# SKAARDUINO_v3_1_bottom.net
KiCad netlist of a schematic drawn in EAGLE
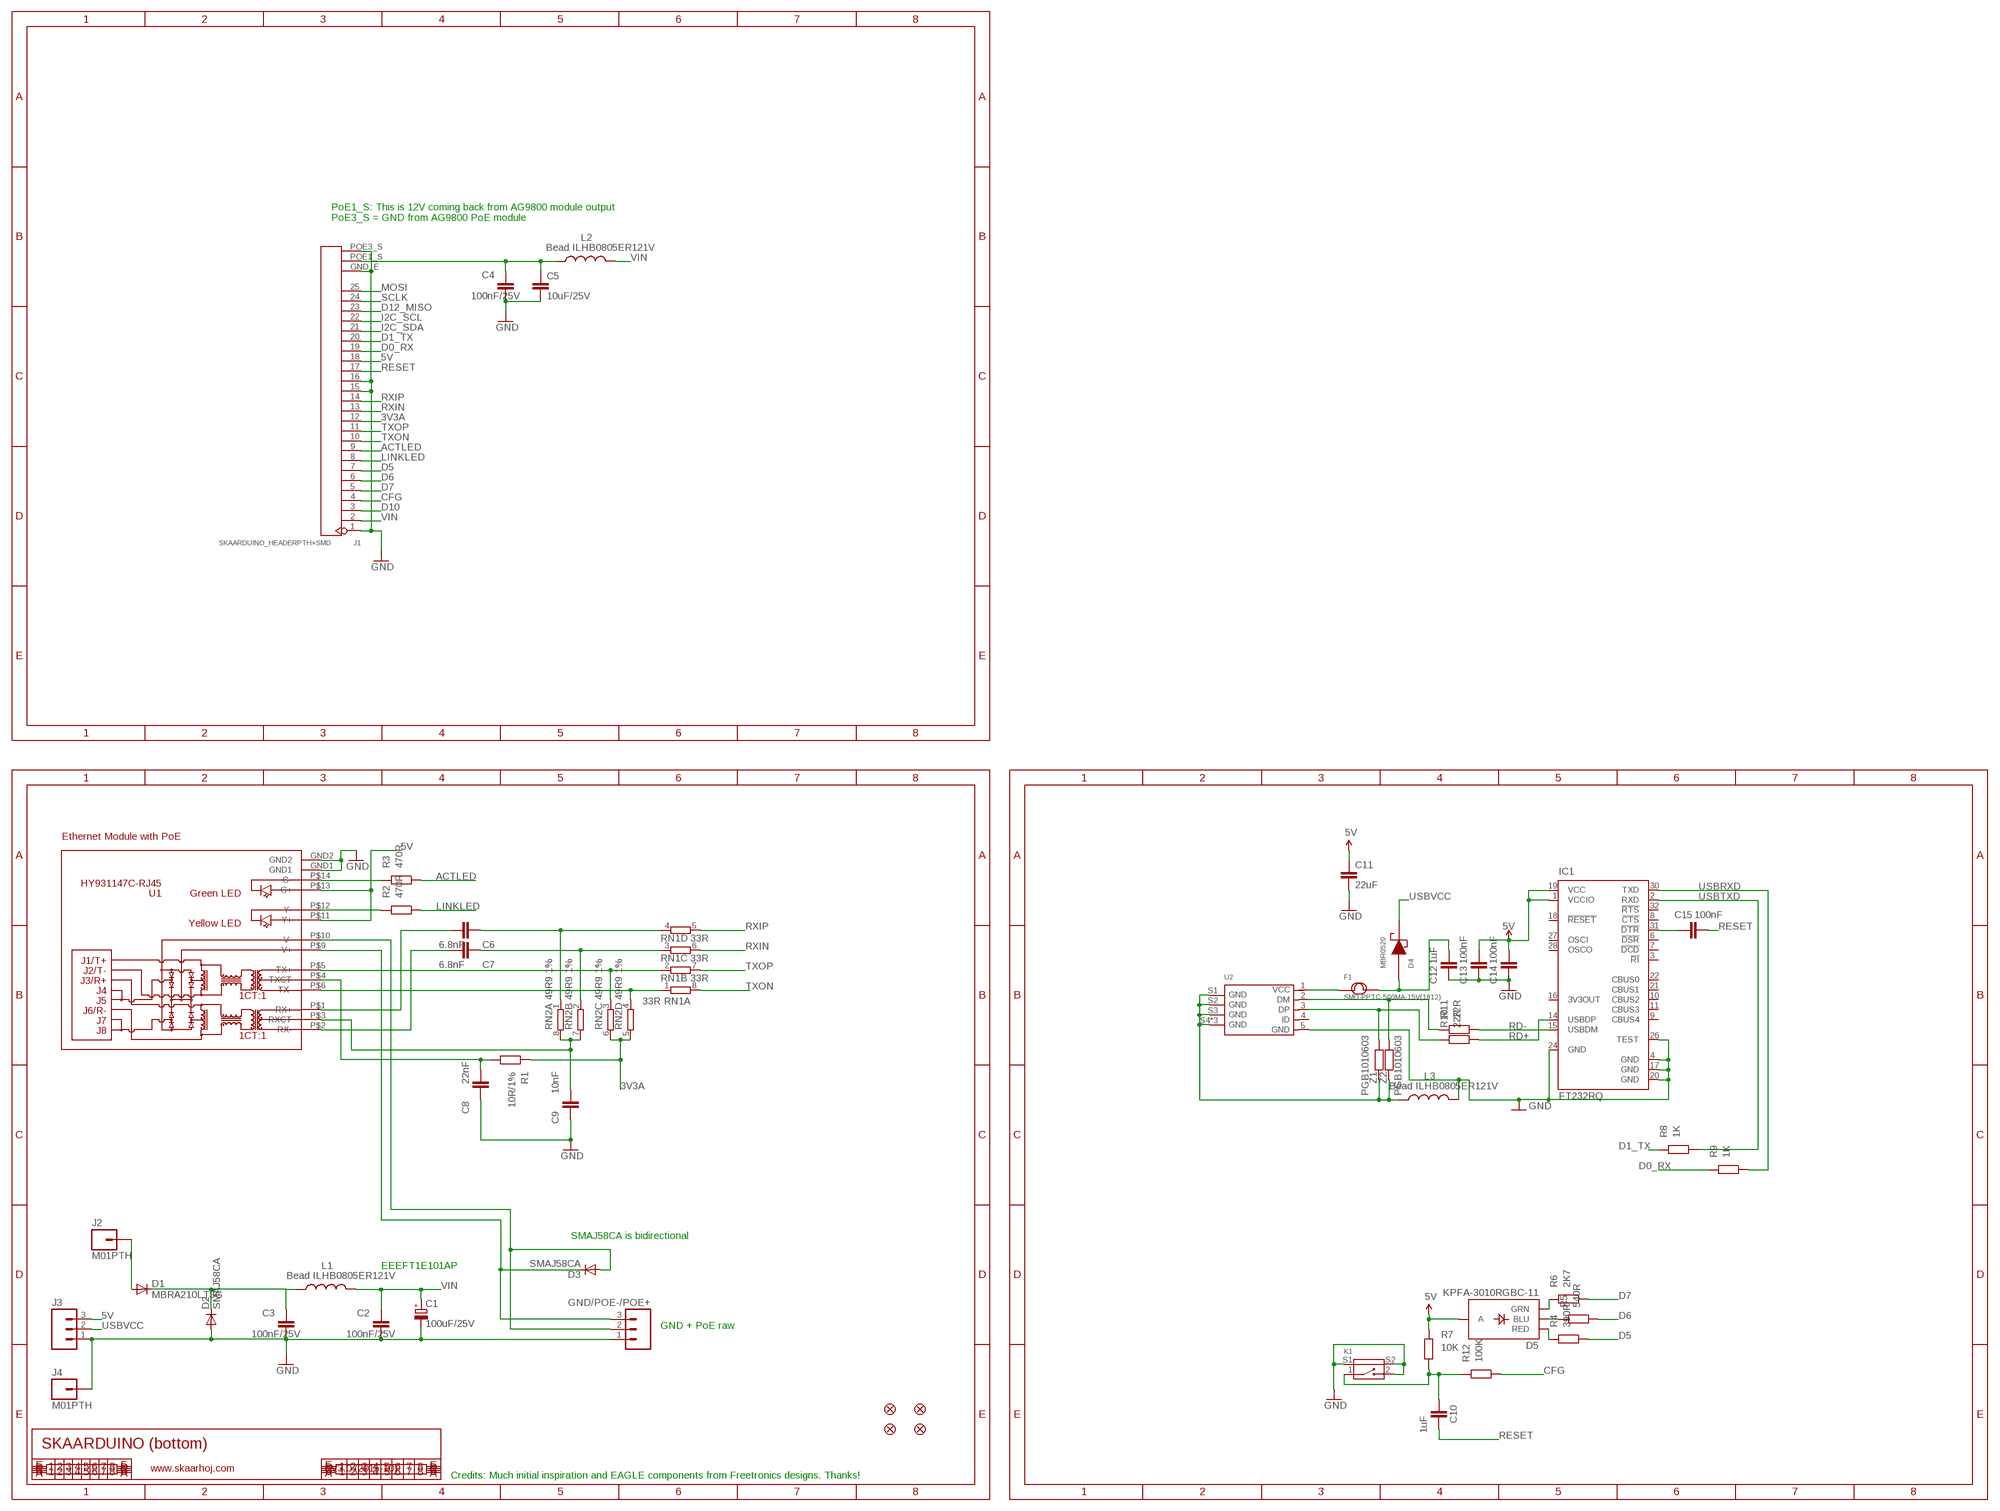
[diagram p0: schematic, sheet 1]

(export (version "E")
  (design (tool "Eeschema 10.0.6"))
  (components
    (comp (ref "C1")
      (value "100uF/25V")
      (footprint "eagle-import:PANASONIC_D")
      (libsource (lib "eagle-import") (part "CPOL-EUD"))
    )
    (comp (ref "C2")
      (value "100nF/25V")
      (footprint "eagle-import:C0402")
      (libsource (lib "eagle-import") (part "CAP0402"))
    )
    (comp (ref "C3")
      (value "100nF/25V")
      (footprint "eagle-import:C0402")
      (libsource (lib "eagle-import") (part "CAP0402"))
    )
    (comp (ref "C4")
      (value "100nF/25V")
      (footprint "eagle-import:C0402")
      (libsource (lib "eagle-import") (part "CAP0402"))
    )
    (comp (ref "C5")
      (value "10uF/25V")
      (footprint "eagle-import:0805")
      (libsource (lib "eagle-import") (part "CAP0805"))
    )
    (comp (ref "C6")
      (value "6.8nF")
      (footprint "eagle-import:0402C")
      (libsource (lib "eagle-import") (part "C-EU0402C"))
    )
    (comp (ref "C7")
      (value "6.8nF")
      (footprint "eagle-import:0402C")
      (libsource (lib "eagle-import") (part "C-EU0402C"))
    )
    (comp (ref "C8")
      (value "22nF")
      (footprint "eagle-import:0402C")
      (libsource (lib "eagle-import") (part "C-EU0402C"))
    )
    (comp (ref "C9")
      (value "10nF")
      (footprint "eagle-import:0402C")
      (libsource (lib "eagle-import") (part "C-EU0402C"))
    )
    (comp (ref "C10")
      (value "1uF")
      (footprint "eagle-import:0402C")
      (libsource (lib "eagle-import") (part "C-EU0402C"))
    )
    (comp (ref "C11")
      (value "22uF")
      (footprint "eagle-import:0805")
      (libsource (lib "eagle-import") (part "CAP0805"))
    )
    (comp (ref "C12")
      (value "1uF")
      (footprint "eagle-import:0402C")
      (libsource (lib "eagle-import") (part "C-EU0402C"))
    )
    (comp (ref "C13")
      (value "100nF")
      (footprint "eagle-import:0402C")
      (libsource (lib "eagle-import") (part "C-EU0402C"))
    )
    (comp (ref "C14")
      (value "100nF")
      (footprint "eagle-import:0402C")
      (libsource (lib "eagle-import") (part "C-EU0402C"))
    )
    (comp (ref "C15")
      (value "100nF")
      (footprint "eagle-import:0402C")
      (libsource (lib "eagle-import") (part "C-EU0402C"))
    )
    (comp (ref "D1")
      (value "MBRA210LT3G")
      (footprint "eagle-import:SMA-DIODE")
      (libsource (lib "eagle-import") (part "DIODESMA"))
    )
    (comp (ref "D2")
      (value "SMAJ58CA")
      (footprint "eagle-import:SMA-DIODE")
      (libsource (lib "eagle-import") (part "DIODESMA"))
    )
    (comp (ref "D3")
      (value "SMAJ58CA")
      (footprint "eagle-import:SMA-DIODE")
      (libsource (lib "eagle-import") (part "DIODESMA"))
    )
    (comp (ref "D4")
      (value "MBR0520")
      (footprint "eagle-import:SOD-123")
      (libsource (lib "eagle-import") (part "MBR0520"))
    )
    (comp (ref "D5")
      (value "KPFA-3010RGBC-11")
      (footprint "eagle-import:LED-TRICOLOR-SMD")
      (libsource (lib "eagle-import") (part "LED-TRICOLOR"))
    )
    (comp (ref "F1")
      (value "SMD-PPTC-500MA-15V(1812)")
      (footprint "eagle-import:F1812")
      (libsource (lib "eagle-import") (part "SMD-PPTC-500MA-15V(1812)"))
    )
    (comp (ref "FID1")
      (value "FIDUCIAL1X2.5")
      (footprint "eagle-import:FIDUCIAL-1X2.5")
      (libsource (lib "eagle-import") (part "FIDUCIAL1X2.5"))
    )
    (comp (ref "FID2")
      (value "FIDUCIAL1X2.5")
      (footprint "eagle-import:FIDUCIAL-1X2.5")
      (libsource (lib "eagle-import") (part "FIDUCIAL1X2.5"))
    )
    (comp (ref "FID3")
      (value "FIDUCIAL1X2.5")
      (footprint "eagle-import:FIDUCIAL-1X2.5")
      (libsource (lib "eagle-import") (part "FIDUCIAL1X2.5"))
    )
    (comp (ref "FID4")
      (value "FIDUCIAL1X2.5")
      (footprint "eagle-import:FIDUCIAL-1X2.5")
      (libsource (lib "eagle-import") (part "FIDUCIAL1X2.5"))
    )
    (comp (ref "GND/POE-/POE+")
      (value "M03LOCK")
      (footprint "eagle-import:1X03_LOCK")
      (libsource (lib "eagle-import") (part "M03LOCK"))
    )
    (comp (ref "IC1")
      (value "FT232RQ")
      (footprint "eagle-import:QFN32")
      (libsource (lib "eagle-import") (part "FT232RQ"))
    )
    (comp (ref "J1")
      (value "SKAARDUINO_HEADERPTH+SMD")
      (footprint "eagle-import:SKAARDUINO_PTH_SMD_HEADER")
      (libsource (lib "eagle-import") (part "SKAARDUINO_HEADERPTH+SMD"))
    )
    (comp (ref "J2")
      (value "M01PTH")
      (footprint "eagle-import:1X01")
      (libsource (lib "eagle-import") (part "M01PTH"))
    )
    (comp (ref "J3")
      (value "M03LOCK")
      (footprint "eagle-import:1X03_LOCK")
      (libsource (lib "eagle-import") (part "M03LOCK"))
    )
    (comp (ref "J4")
      (value "M01PTH")
      (footprint "eagle-import:1X01")
      (libsource (lib "eagle-import") (part "M01PTH"))
    )
    (comp (ref "K1")
      (value "SMD-BUTTON-2+2P")
      (footprint "eagle-import:SW4-SMD-7.0X3.5X3.5MM-90D")
      (fields (field (name "MPN") "TS-1188E"))
      (libsource (lib "eagle-import") (part "SMD-BUTTON-2+2P"))
    )
    (comp (ref "L1")
      (value "Bead ILHB0805ER121V")
      (footprint "eagle-import:L2012C")
      (libsource (lib "eagle-import") (part "L-USL2012C"))
    )
    (comp (ref "L2")
      (value "Bead ILHB0805ER121V")
      (footprint "eagle-import:L2012C")
      (libsource (lib "eagle-import") (part "L-USL2012C"))
    )
    (comp (ref "L3")
      (value "Bead ILHB0805ER121V")
      (footprint "eagle-import:L2012C")
      (libsource (lib "eagle-import") (part "L-USL2012C"))
    )
    (comp (ref "R1")
      (value "10R/1%")
      (footprint "eagle-import:0402")
      (libsource (lib "eagle-import") (part "freetronics-jon_RESISTOR0402"))
    )
    (comp (ref "R2")
      (value "470R")
      (footprint "eagle-import:0402")
      (libsource (lib "eagle-import") (part "freetronics-jon_RESISTOR0402"))
    )
    (comp (ref "R3")
      (value "470R")
      (footprint "eagle-import:0402")
      (libsource (lib "eagle-import") (part "freetronics-jon_RESISTOR0402"))
    )
    (comp (ref "R4")
      (value "390R")
      (footprint "eagle-import:0402")
      (libsource (lib "eagle-import") (part "freetronics-jon_RESISTOR0402"))
    )
    (comp (ref "R5")
      (value "540R")
      (footprint "eagle-import:0402")
      (libsource (lib "eagle-import") (part "freetronics-jon_RESISTOR0402"))
    )
    (comp (ref "R6")
      (value "2K7")
      (footprint "eagle-import:0402")
      (libsource (lib "eagle-import") (part "freetronics-jon_RESISTOR0402"))
    )
    (comp (ref "R7")
      (value "10K")
      (footprint "eagle-import:0402")
      (libsource (lib "eagle-import") (part "freetronics-jon_RESISTOR0402"))
    )
    (comp (ref "R8")
      (value "1K")
      (footprint "eagle-import:0402")
      (libsource (lib "eagle-import") (part "freetronics-jon_RESISTOR0402"))
    )
    (comp (ref "R9")
      (value "1K")
      (footprint "eagle-import:0402")
      (libsource (lib "eagle-import") (part "freetronics-jon_RESISTOR0402"))
    )
    (comp (ref "R10")
      (value "22R")
      (footprint "eagle-import:0402")
      (libsource (lib "eagle-import") (part "freetronics-jon_RESISTOR0402"))
    )
    (comp (ref "R11")
      (value "22R")
      (footprint "eagle-import:0402")
      (libsource (lib "eagle-import") (part "freetronics-jon_RESISTOR0402"))
    )
    (comp (ref "R12")
      (value "100K")
      (footprint "eagle-import:0402")
      (libsource (lib "eagle-import") (part "freetronics-jon_RESISTOR0402"))
    )
    (comp (ref "RN1")
      (value "33R")
      (footprint "eagle-import:CAY16")
      (libsource (lib "eagle-import") (part "4R-NCAY16"))
    )
    (comp (ref "RN2")
      (value "49R9 1%")
      (footprint "eagle-import:CAY16")
      (libsource (lib "eagle-import") (part "4R-NCAY16"))
    )
    (comp (ref "U1")
      (value "HY931147C-RJ45")
      (footprint "eagle-import:HY931147C")
      (libsource (lib "eagle-import") (part "HY931147C-RJ45"))
    )
    (comp (ref "U2")
      (value "MICRO-USB-SMD-B-WITHOUT-POST-W/P(ST-USB-001G)")
      (footprint "eagle-import:MICRO-USB5+4P-SMD-0.65-B")
      (fields (field (name "MPN") "ST-USB-001G"))
      (libsource (lib "eagle-import") (part "MICRO-USB-SMD-B-WITHOUT-POST-W/P(ST-USB-001G)"))
    )
    (comp (ref "Z1")
      (value "PGB1010603")
      (footprint "eagle-import:C0402")
      (libsource (lib "eagle-import") (part "RESISTOR0402"))
    )
    (comp (ref "Z2")
      (value "PGB1010603")
      (footprint "eagle-import:C0402")
      (libsource (lib "eagle-import") (part "RESISTOR0402"))
    )
  )
  (nets
    (net (code "1") (name "/3V3A") (class "Default")
      (node (ref "J1") (pin "12") (pinfunction "12_12") (pintype "bidirectional"))
      (node (ref "R1") (pin "2") (pinfunction "2_2") (pintype "passive"))
      (node (ref "RN2") (pin "5") (pinfunction "2_5") (pintype "passive"))
      (node (ref "RN2") (pin "6") (pinfunction "2_6") (pintype "passive"))
    )
    (net (code "2") (name "/ACTLED") (class "Default")
      (node (ref "J1") (pin "9") (pinfunction "9_9") (pintype "bidirectional"))
      (node (ref "R3") (pin "1") (pinfunction "1_1") (pintype "passive"))
    )
    (net (code "3") (name "/CFG") (class "Default")
      (node (ref "J1") (pin "4") (pinfunction "4_4") (pintype "bidirectional"))
      (node (ref "R12") (pin "1") (pinfunction "1_1") (pintype "passive"))
    )
    (net (code "4") (name "/D0_RX") (class "Default")
      (node (ref "J1") (pin "19") (pinfunction "19_19") (pintype "bidirectional"))
      (node (ref "R9") (pin "2") (pinfunction "2_2") (pintype "passive"))
    )
    (net (code "5") (name "/D1_TX") (class "Default")
      (node (ref "J1") (pin "20") (pinfunction "20_20") (pintype "bidirectional"))
      (node (ref "R8") (pin "2") (pinfunction "2_2") (pintype "passive"))
    )
    (net (code "6") (name "/D5") (class "Default")
      (node (ref "J1") (pin "7") (pinfunction "7_7") (pintype "bidirectional"))
      (node (ref "R4") (pin "1") (pinfunction "1_1") (pintype "passive"))
    )
    (net (code "7") (name "/D6") (class "Default")
      (node (ref "J1") (pin "6") (pinfunction "6_6") (pintype "bidirectional"))
      (node (ref "R5") (pin "1") (pinfunction "1_1") (pintype "passive"))
    )
    (net (code "8") (name "/D7") (class "Default")
      (node (ref "J1") (pin "5") (pinfunction "5_5") (pintype "bidirectional"))
      (node (ref "R6") (pin "1") (pinfunction "1_1") (pintype "passive"))
    )
    (net (code "9") (name "/D10") (class "Default")
      (node (ref "J1") (pin "3") (pinfunction "3_3") (pintype "bidirectional"))
    )
    (net (code "10") (name "/D12_MISO") (class "Default")
      (node (ref "J1") (pin "23") (pinfunction "23_23") (pintype "bidirectional"))
    )
    (net (code "11") (name "/I2C_SCL") (class "Default")
      (node (ref "J1") (pin "22") (pinfunction "22_22") (pintype "bidirectional"))
    )
    (net (code "12") (name "/I2C_SDA") (class "Default")
      (node (ref "J1") (pin "21") (pinfunction "21_21") (pintype "bidirectional"))
    )
    (net (code "13") (name "/LINKLED") (class "Default")
      (node (ref "J1") (pin "8") (pinfunction "8_8") (pintype "bidirectional"))
      (node (ref "R2") (pin "1") (pinfunction "1_1") (pintype "passive"))
    )
    (net (code "14") (name "/MOSI") (class "Default")
      (node (ref "J1") (pin "25") (pinfunction "25_25") (pintype "bidirectional"))
    )
    (net (code "15") (name "/RD+") (class "Default")
      (node (ref "IC1") (pin "14") (pinfunction "USBDP_14") (pintype "bidirectional"))
      (node (ref "R10") (pin "1") (pinfunction "1_1") (pintype "passive"))
    )
    (net (code "16") (name "/RD-") (class "Default")
      (node (ref "IC1") (pin "15") (pinfunction "USBDM_15") (pintype "bidirectional"))
      (node (ref "R11") (pin "1") (pinfunction "1_1") (pintype "passive"))
    )
    (net (code "17") (name "/RESET") (class "Default")
      (node (ref "C10") (pin "1") (pinfunction "1_1") (pintype "passive"))
      (node (ref "C15") (pin "2") (pinfunction "2_2") (pintype "passive"))
      (node (ref "J1") (pin "17") (pinfunction "17_17") (pintype "bidirectional"))
    )
    (net (code "18") (name "/RXIN") (class "Default")
      (node (ref "J1") (pin "13") (pinfunction "13_13") (pintype "bidirectional"))
      (node (ref "RN1") (pin "6") (pinfunction "2_6") (pintype "passive"))
    )
    (net (code "19") (name "/RXIP") (class "Default")
      (node (ref "J1") (pin "14") (pinfunction "14_14") (pintype "bidirectional"))
      (node (ref "RN1") (pin "5") (pinfunction "2_5") (pintype "passive"))
    )
    (net (code "20") (name "/SCLK") (class "Default")
      (node (ref "J1") (pin "24") (pinfunction "24_24") (pintype "bidirectional"))
    )
    (net (code "21") (name "/TXON") (class "Default")
      (node (ref "J1") (pin "10") (pinfunction "10_10") (pintype "bidirectional"))
      (node (ref "RN1") (pin "8") (pinfunction "2_8") (pintype "passive"))
    )
    (net (code "22") (name "/TXOP") (class "Default")
      (node (ref "J1") (pin "11") (pinfunction "11_11") (pintype "bidirectional"))
      (node (ref "RN1") (pin "7") (pinfunction "2_7") (pintype "passive"))
    )
    (net (code "23") (name "/USBRXD") (class "Default")
      (node (ref "IC1") (pin "30") (pinfunction "TXD_30") (pintype "output"))
      (node (ref "R9") (pin "1") (pinfunction "1_1") (pintype "passive"))
    )
    (net (code "24") (name "/USBTXD") (class "Default")
      (node (ref "IC1") (pin "2") (pinfunction "RXD_2") (pintype "input"))
      (node (ref "R8") (pin "1") (pinfunction "1_1") (pintype "passive"))
    )
    (net (code "25") (name "/USBVCC") (class "Default")
      (node (ref "D4") (pin "1") (pinfunction "CA_1") (pintype "passive"))
      (node (ref "J3") (pin "2") (pinfunction "2_2") (pintype "passive"))
    )
    (net (code "26") (name "/VIN") (class "Default")
      (node (ref "C1") (pin "+") (pinfunction "+_+") (pintype "passive"))
      (node (ref "C2") (pin "1") (pinfunction "1_1") (pintype "passive"))
      (node (ref "J1") (pin "2") (pinfunction "2_2") (pintype "bidirectional"))
      (node (ref "L1") (pin "2") (pinfunction "2_2") (pintype "passive"))
      (node (ref "L2") (pin "2") (pinfunction "2_2") (pintype "passive"))
    )
    (net (code "27") (name "5V") (class "Default")
      (node (ref "C11") (pin "1") (pinfunction "1_1") (pintype "passive"))
      (node (ref "C13") (pin "2") (pinfunction "2_2") (pintype "passive"))
      (node (ref "C14") (pin "2") (pinfunction "2_2") (pintype "passive"))
      (node (ref "D5") (pin "A") (pinfunction "A_A") (pintype "bidirectional"))
      (node (ref "IC1") (pin "1") (pinfunction "VCCIO_1") (pintype "power_in"))
      (node (ref "IC1") (pin "19") (pinfunction "VCC_19") (pintype "power_in"))
      (node (ref "J1") (pin "18") (pinfunction "18_18") (pintype "bidirectional"))
      (node (ref "J3") (pin "3") (pinfunction "3_3") (pintype "passive"))
      (node (ref "R7") (pin "2") (pinfunction "2_2") (pintype "passive"))
      (node (ref "U1") (pin "P$11") (pinfunction "Y+_P$11") (pintype "bidirectional"))
      (node (ref "U1") (pin "P$13") (pinfunction "G+_P$13") (pintype "bidirectional"))
    )
    (net (code "28") (name "GND") (class "Default")
      (node (ref "C1") (pin "-") (pinfunction "-_-") (pintype "passive"))
      (node (ref "C11") (pin "2") (pinfunction "2_2") (pintype "passive"))
      (node (ref "C12") (pin "1") (pinfunction "1_1") (pintype "passive"))
      (node (ref "C13") (pin "1") (pinfunction "1_1") (pintype "passive"))
      (node (ref "C14") (pin "1") (pinfunction "1_1") (pintype "passive"))
      (node (ref "C2") (pin "2") (pinfunction "2_2") (pintype "passive"))
      (node (ref "C3") (pin "2") (pinfunction "2_2") (pintype "passive"))
      (node (ref "C4") (pin "2") (pinfunction "2_2") (pintype "passive"))
      (node (ref "C5") (pin "2") (pinfunction "2_2") (pintype "passive"))
      (node (ref "C8") (pin "1") (pinfunction "1_1") (pintype "passive"))
      (node (ref "C9") (pin "1") (pinfunction "1_1") (pintype "passive"))
      (node (ref "D2") (pin "A") (pinfunction "A_A") (pintype "passive"))
      (node (ref "GND/POE-/POE+") (pin "1") (pinfunction "1_1") (pintype "passive"))
      (node (ref "IC1") (pin "17") (pinfunction "GND_17") (pintype "power_in"))
      (node (ref "IC1") (pin "20") (pinfunction "GND_20") (pintype "power_in"))
      (node (ref "IC1") (pin "24") (pinfunction "GND_24") (pintype "power_in"))
      (node (ref "IC1") (pin "26") (pinfunction "TEST_26") (pintype "input"))
      (node (ref "IC1") (pin "4") (pinfunction "GND_4") (pintype "power_in"))
      (node (ref "J1") (pin "1") (pinfunction "1_1") (pintype "bidirectional"))
      (node (ref "J1") (pin "15") (pinfunction "15_15") (pintype "bidirectional"))
      (node (ref "J1") (pin "16") (pinfunction "16_16") (pintype "bidirectional"))
      (node (ref "J1") (pin "GND_E") (pinfunction "26_GND_E") (pintype "bidirectional"))
      (node (ref "J1") (pin "POE3_S") (pinfunction "28_POE3_S") (pintype "bidirectional"))
      (node (ref "J3") (pin "1") (pinfunction "1_1") (pintype "passive"))
      (node (ref "J4") (pin "1") (pinfunction "1_1") (pintype "passive"))
      (node (ref "K1") (pin "2") (pinfunction "2_2") (pintype "bidirectional"))
      (node (ref "K1") (pin "S1") (pinfunction "S1_S1") (pintype "bidirectional"))
      (node (ref "K1") (pin "S2") (pinfunction "S2_S2") (pintype "bidirectional"))
      (node (ref "L3") (pin "2") (pinfunction "2_2") (pintype "passive"))
      (node (ref "U1") (pin "GND1") (pinfunction "GND1_GND1") (pintype "bidirectional"))
      (node (ref "U1") (pin "GND2") (pinfunction "GND2_GND2") (pintype "bidirectional"))
      (node (ref "U2") (pin "5") (pinfunction "GND_5") (pintype "bidirectional"))
    )
    (net (code "29") (name "Net-(C3-Pad1)") (class "Default")
      (node (ref "C3") (pin "1") (pinfunction "1_1") (pintype "passive"))
      (node (ref "D1") (pin "C") (pinfunction "C_C") (pintype "passive"))
      (node (ref "D2") (pin "C") (pinfunction "C_C") (pintype "passive"))
      (node (ref "L1") (pin "1") (pinfunction "1_1") (pintype "passive"))
    )
    (net (code "30") (name "Net-(C10-Pad2)") (class "Default")
      (node (ref "C10") (pin "2") (pinfunction "2_2") (pintype "passive"))
      (node (ref "K1") (pin "1") (pinfunction "1_1") (pintype "bidirectional"))
      (node (ref "R12") (pin "2") (pinfunction "2_2") (pintype "passive"))
      (node (ref "R7") (pin "1") (pinfunction "1_1") (pintype "passive"))
    )
    (net (code "31") (name "Net-(D1-PadA)") (class "Default")
      (node (ref "D1") (pin "A") (pinfunction "A_A") (pintype "passive"))
      (node (ref "J2") (pin "1") (pinfunction "1_1") (pintype "passive"))
    )
    (net (code "32") (name "Net-(D4-AN)") (class "Default")
      (node (ref "C12") (pin "2") (pinfunction "2_2") (pintype "passive"))
      (node (ref "D4") (pin "2") (pinfunction "AN_2") (pintype "passive"))
      (node (ref "F1") (pin "2") (pinfunction "2_2") (pintype "bidirectional"))
    )
    (net (code "33") (name "Net-(D5-BLU)") (class "Default")
      (node (ref "D5") (pin "B") (pinfunction "BLU_B") (pintype "bidirectional"))
      (node (ref "R5") (pin "2") (pinfunction "2_2") (pintype "passive"))
    )
    (net (code "34") (name "Net-(D5-GRN)") (class "Default")
      (node (ref "D5") (pin "G") (pinfunction "GRN_G") (pintype "bidirectional"))
      (node (ref "R6") (pin "2") (pinfunction "2_2") (pintype "passive"))
    )
    (net (code "35") (name "Net-(D5-RED)") (class "Default")
      (node (ref "D5") (pin "R") (pinfunction "RED_R") (pintype "bidirectional"))
      (node (ref "R4") (pin "2") (pinfunction "2_2") (pintype "passive"))
    )
    (net (code "36") (name "Net-(IC1-~{DTR})") (class "Default")
      (node (ref "C15") (pin "1") (pinfunction "1_1") (pintype "passive"))
      (node (ref "IC1") (pin "31") (pinfunction "~{DTR}_31") (pintype "output"))
    )
    (net (code "37") (name "Net-(J1-27)") (class "Default")
      (node (ref "C4") (pin "1") (pinfunction "1_1") (pintype "passive"))
      (node (ref "C5") (pin "1") (pinfunction "1_1") (pintype "passive"))
      (node (ref "J1") (pin "POE1_S") (pinfunction "27_POE1_S") (pintype "bidirectional"))
      (node (ref "L2") (pin "1") (pinfunction "1_1") (pintype "passive"))
    )
    (net (code "38") (name "Net-(L3-Pad1)") (class "Default")
      (node (ref "L3") (pin "1") (pinfunction "1_1") (pintype "passive"))
      (node (ref "U2") (pin "S1") (pinfunction "GND_S1") (pintype "bidirectional"))
      (node (ref "U2") (pin "S2") (pinfunction "GND_S2") (pintype "bidirectional"))
      (node (ref "U2") (pin "S3") (pinfunction "GND_S3") (pintype "bidirectional"))
      (node (ref "U2") (pin "S4") (pinfunction "GND_S4") (pintype "bidirectional"))
      (node (ref "U2") (pin "S5") (pinfunction "GND_S5") (pintype "bidirectional"))
      (node (ref "U2") (pin "S6") (pinfunction "GND_S6") (pintype "bidirectional"))
      (node (ref "Z1") (pin "2") (pinfunction "2_2") (pintype "passive"))
      (node (ref "Z2") (pin "2") (pinfunction "2_2") (pintype "passive"))
    )
    (net (code "39") (name "Net-(RN1B-1)") (class "Default")
      (node (ref "RN1") (pin "2") (pinfunction "1_2") (pintype "passive"))
      (node (ref "RN2") (pin "3") (pinfunction "1_3") (pintype "passive"))
      (node (ref "U1") (pin "P$5") (pinfunction "TX+_P$5") (pintype "bidirectional"))
    )
    (net (code "40") (name "Net-(RN1C-1)") (class "Default")
      (node (ref "C7") (pin "1") (pinfunction "1_1") (pintype "passive"))
      (node (ref "RN1") (pin "3") (pinfunction "1_3") (pintype "passive"))
      (node (ref "RN2") (pin "2") (pinfunction "1_2") (pintype "passive"))
    )
    (net (code "41") (name "Net-(RN1D-1)") (class "Default")
      (node (ref "C6") (pin "1") (pinfunction "1_1") (pintype "passive"))
      (node (ref "RN1") (pin "4") (pinfunction "1_4") (pintype "passive"))
      (node (ref "RN2") (pin "1") (pinfunction "1_1") (pintype "passive"))
    )
    (net (code "42") (name "Net-(RN2A-2)") (class "Default")
      (node (ref "C9") (pin "2") (pinfunction "2_2") (pintype "passive"))
      (node (ref "RN2") (pin "7") (pinfunction "2_7") (pintype "passive"))
      (node (ref "RN2") (pin "8") (pinfunction "2_8") (pintype "passive"))
      (node (ref "U1") (pin "P$3") (pinfunction "RXCT_P$3") (pintype "bidirectional"))
    )
    (net (code "43") (name "Net-(RN2D-1)") (class "Default")
      (node (ref "RN1") (pin "1") (pinfunction "1_1") (pintype "passive"))
      (node (ref "RN2") (pin "4") (pinfunction "1_4") (pintype "passive"))
      (node (ref "U1") (pin "P$6") (pinfunction "TX-_P$6") (pintype "bidirectional"))
    )
    (net (code "44") (name "Net-(U1-G-)") (class "Default")
      (node (ref "R3") (pin "2") (pinfunction "2_2") (pintype "passive"))
      (node (ref "U1") (pin "P$14") (pinfunction "G-_P$14") (pintype "bidirectional"))
    )
    (net (code "45") (name "Net-(U1-RX+)") (class "Default")
      (node (ref "C6") (pin "2") (pinfunction "2_2") (pintype "passive"))
      (node (ref "U1") (pin "P$1") (pinfunction "RX+_P$1") (pintype "bidirectional"))
    )
    (net (code "46") (name "Net-(U1-RX-)") (class "Default")
      (node (ref "C7") (pin "2") (pinfunction "2_2") (pintype "passive"))
      (node (ref "U1") (pin "P$2") (pinfunction "RX-_P$2") (pintype "bidirectional"))
    )
    (net (code "47") (name "Net-(U1-TXCT)") (class "Default")
      (node (ref "C8") (pin "2") (pinfunction "2_2") (pintype "passive"))
      (node (ref "R1") (pin "1") (pinfunction "1_1") (pintype "passive"))
      (node (ref "U1") (pin "P$4") (pinfunction "TXCT_P$4") (pintype "bidirectional"))
    )
    (net (code "48") (name "Net-(U1-V+)") (class "Default")
      (node (ref "D3") (pin "C") (pinfunction "C_C") (pintype "passive"))
      (node (ref "GND/POE-/POE+") (pin "3") (pinfunction "3_3") (pintype "passive"))
      (node (ref "U1") (pin "P$9") (pinfunction "V+_P$9") (pintype "bidirectional"))
    )
    (net (code "49") (name "Net-(U1-V-)") (class "Default")
      (node (ref "D3") (pin "A") (pinfunction "A_A") (pintype "passive"))
      (node (ref "GND/POE-/POE+") (pin "2") (pinfunction "2_2") (pintype "passive"))
      (node (ref "U1") (pin "P$10") (pinfunction "V-_P$10") (pintype "bidirectional"))
    )
    (net (code "50") (name "Net-(U1-Y-)") (class "Default")
      (node (ref "R2") (pin "2") (pinfunction "2_2") (pintype "passive"))
      (node (ref "U1") (pin "P$12") (pinfunction "Y-_P$12") (pintype "bidirectional"))
    )
    (net (code "51") (name "Net-(U2-DM)") (class "Default")
      (node (ref "R11") (pin "2") (pinfunction "2_2") (pintype "passive"))
      (node (ref "U2") (pin "2") (pinfunction "DM_2") (pintype "bidirectional"))
      (node (ref "Z2") (pin "1") (pinfunction "1_1") (pintype "passive"))
    )
    (net (code "52") (name "Net-(U2-DP)") (class "Default")
      (node (ref "R10") (pin "2") (pinfunction "2_2") (pintype "passive"))
      (node (ref "U2") (pin "3") (pinfunction "DP_3") (pintype "bidirectional"))
      (node (ref "Z1") (pin "1") (pinfunction "1_1") (pintype "passive"))
    )
    (net (code "53") (name "Net-(U2-VCC)") (class "Default")
      (node (ref "F1") (pin "1") (pinfunction "1_1") (pintype "bidirectional"))
      (node (ref "U2") (pin "1") (pinfunction "VCC_1") (pintype "bidirectional"))
    )
    (net (code "54") (name "unconnected-(IC1-3V3OUT-Pad16)") (class "Default")
      (node (ref "IC1") (pin "16") (pinfunction "3V3OUT_16") (pintype "output"))
    )
    (net (code "55") (name "unconnected-(IC1-CBUS0-Pad22)") (class "Default")
      (node (ref "IC1") (pin "22") (pinfunction "CBUS0_22") (pintype "bidirectional"))
    )
    (net (code "56") (name "unconnected-(IC1-CBUS1-Pad21)") (class "Default")
      (node (ref "IC1") (pin "21") (pinfunction "CBUS1_21") (pintype "bidirectional"))
    )
    (net (code "57") (name "unconnected-(IC1-CBUS2-Pad10)") (class "Default")
      (node (ref "IC1") (pin "10") (pinfunction "CBUS2_10") (pintype "bidirectional"))
    )
    (net (code "58") (name "unconnected-(IC1-CBUS3-Pad11)") (class "Default")
      (node (ref "IC1") (pin "11") (pinfunction "CBUS3_11") (pintype "bidirectional"))
    )
    (net (code "59") (name "unconnected-(IC1-CBUS4-Pad9)") (class "Default")
      (node (ref "IC1") (pin "9") (pinfunction "CBUS4_9") (pintype "bidirectional"))
    )
    (net (code "60") (name "unconnected-(IC1-OSCI-Pad27)") (class "Default")
      (node (ref "IC1") (pin "27") (pinfunction "OSCI_27") (pintype "input"))
    )
    (net (code "61") (name "unconnected-(IC1-OSCO-Pad28)") (class "Default")
      (node (ref "IC1") (pin "28") (pinfunction "OSCO_28") (pintype "output"))
    )
    (net (code "62") (name "unconnected-(IC1-~{CTS}-Pad8)") (class "Default")
      (node (ref "IC1") (pin "8") (pinfunction "~{CTS}_8") (pintype "input"))
    )
    (net (code "63") (name "unconnected-(IC1-~{DCD}-Pad7)") (class "Default")
      (node (ref "IC1") (pin "7") (pinfunction "~{DCD}_7") (pintype "input"))
    )
    (net (code "64") (name "unconnected-(IC1-~{DSR}-Pad6)") (class "Default")
      (node (ref "IC1") (pin "6") (pinfunction "~{DSR}_6") (pintype "input"))
    )
    (net (code "65") (name "unconnected-(IC1-~{RESET}-Pad18)") (class "Default")
      (node (ref "IC1") (pin "18") (pinfunction "~{RESET}_18") (pintype "input"))
    )
    (net (code "66") (name "unconnected-(IC1-~{RI}-Pad3)") (class "Default")
      (node (ref "IC1") (pin "3") (pinfunction "~{RI}_3") (pintype "input"))
    )
    (net (code "67") (name "unconnected-(IC1-~{RTS}-Pad32)") (class "Default")
      (node (ref "IC1") (pin "32") (pinfunction "~{RTS}_32") (pintype "output"))
    )
    (net (code "68") (name "unconnected-(U2-ID-Pad4)") (class "Default")
      (node (ref "U2") (pin "4") (pinfunction "ID_4") (pintype "bidirectional"))
    )
  )
)
